# 13_USB3_0_power.net
KiCad netlist of a schematic drawn in Altium Designer
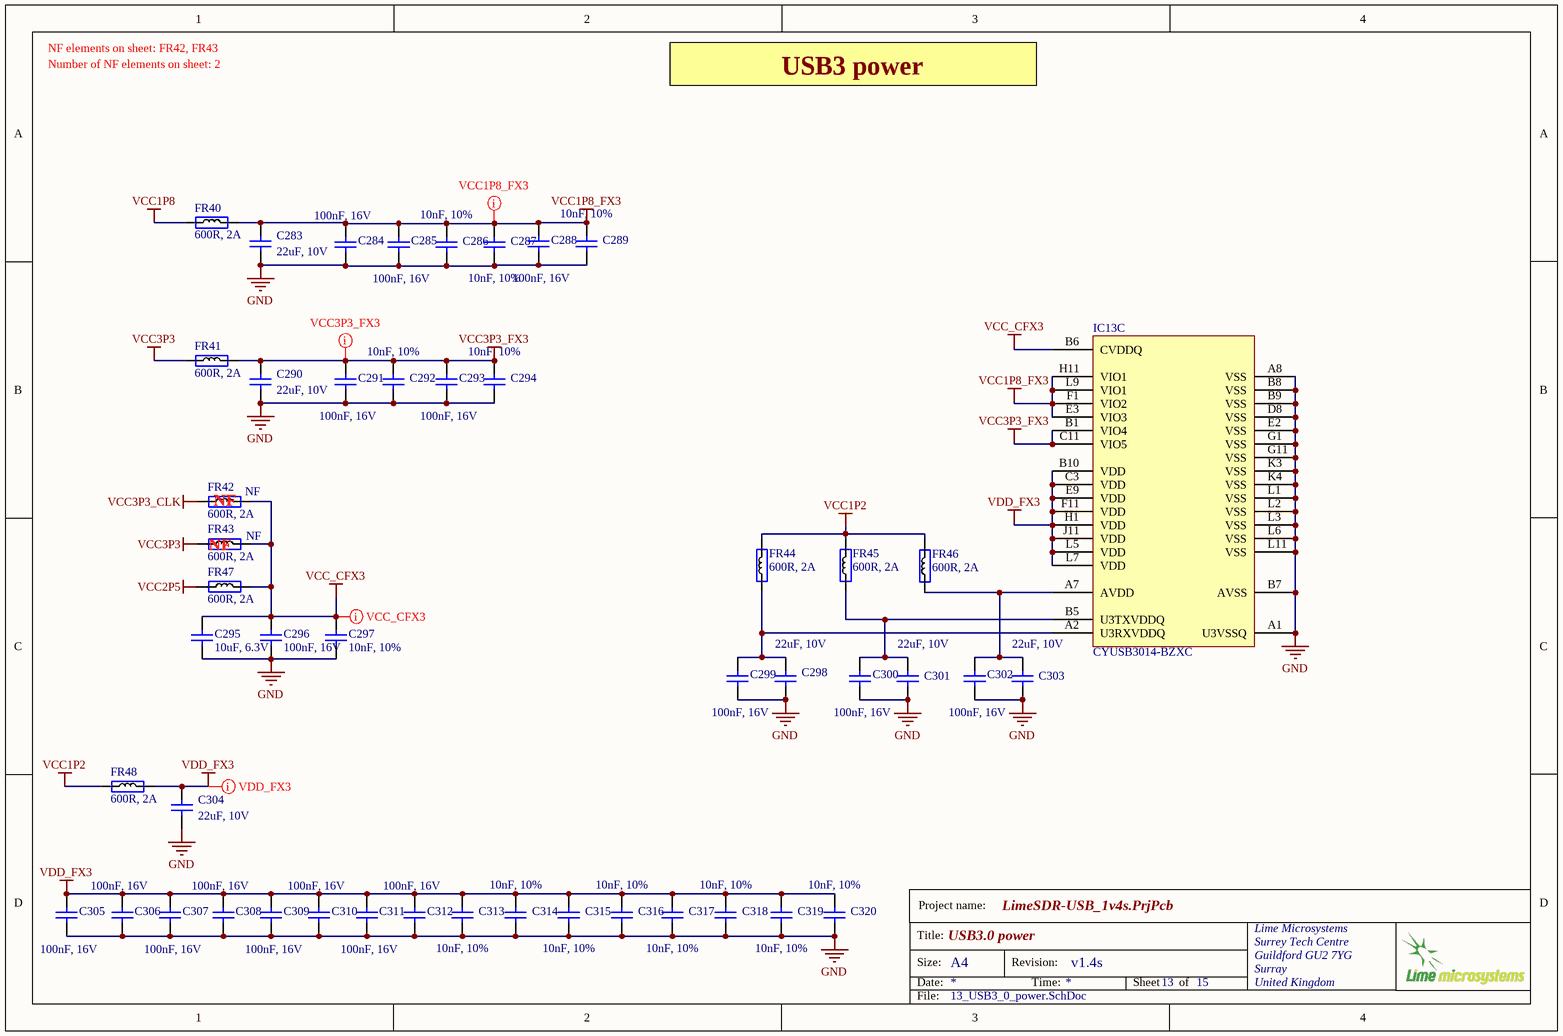
[diagram p0: 13_USB3_0_power.SchDoc]

(export (version "E")
  (design (tool "Eeschema 10.0.6"))
  (components
    (comp (ref "C283")
      (value "22uF, 10V")
      (footprint "CAP0603")
      (fields (field (name "TOLERANCE") "20 %") (field (name "MANUFACTURER") "TDK"))
      (libsource (lib "LimeFPGAboard_schLib") (part "Cap_0603"))
    )
    (comp (ref "C284")
      (value "100nF, 16V")
      (footprint "CAP0402")
      (fields
        (field (name "TOLERANCE") "10 %")
        (field (name "MANUFACTURER") "Murata Electronics")
        (field (name "MANUFACTURER PART NUMBER") "GRM155R71C104KA88D")
      )
      (libsource (lib "LimeFPGAboard_schLib") (part "Cap_0603"))
    )
    (comp (ref "C285")
      (value "100nF, 16V")
      (footprint "CAP0402")
      (fields
        (field (name "TOLERANCE") "10 %")
        (field (name "MANUFACTURER") "Murata Electronics")
        (field (name "MANUFACTURER PART NUMBER") "GRM155R71C104KA88D")
      )
      (libsource (lib "LimeFPGAboard_schLib") (part "Cap_0603"))
    )
    (comp (ref "C286")
      (value "10nF, 10%")
      (footprint "CAP0402")
      (fields (field (name "TOLERANCE") "±10%") (field (name "MANUFACTURER") "Yageo"))
      (libsource (lib "LimeFPGAboard_schLib") (part "Cap_0603"))
    )
    (comp (ref "C287")
      (value "10nF, 10%")
      (footprint "CAP0402")
      (fields (field (name "TOLERANCE") "±10%") (field (name "MANUFACTURER") "Yageo"))
      (libsource (lib "LimeFPGAboard_schLib") (part "Cap_0603"))
    )
    (comp (ref "C288")
      (value "100nF, 16V")
      (footprint "CAP0402")
      (fields
        (field (name "TOLERANCE") "10 %")
        (field (name "MANUFACTURER") "Murata Electronics")
        (field (name "MANUFACTURER PART NUMBER") "GRM155R71C104KA88D")
      )
      (libsource (lib "LimeFPGAboard_schLib") (part "Cap_0603"))
    )
    (comp (ref "C289")
      (value "10nF, 10%")
      (footprint "CAP0402")
      (fields (field (name "TOLERANCE") "±10%") (field (name "MANUFACTURER") "Yageo"))
      (libsource (lib "LimeFPGAboard_schLib") (part "Cap_0603"))
    )
    (comp (ref "C290")
      (value "22uF, 10V")
      (footprint "CAP0603")
      (fields (field (name "TOLERANCE") "20 %") (field (name "MANUFACTURER") "TDK"))
      (libsource (lib "LimeFPGAboard_schLib") (part "Cap_0603"))
    )
    (comp (ref "C291")
      (value "100nF, 16V")
      (footprint "CAP0402")
      (fields
        (field (name "TOLERANCE") "10 %")
        (field (name "MANUFACTURER") "Murata Electronics")
        (field (name "MANUFACTURER PART NUMBER") "GRM155R71C104KA88D")
      )
      (libsource (lib "LimeFPGAboard_schLib") (part "Cap_0603"))
    )
    (comp (ref "C292")
      (value "10nF, 10%")
      (footprint "CAP0402")
      (fields (field (name "TOLERANCE") "±10%") (field (name "MANUFACTURER") "Yageo"))
      (libsource (lib "LimeFPGAboard_schLib") (part "Cap_0603"))
    )
    (comp (ref "C293")
      (value "100nF, 16V")
      (footprint "CAP0402")
      (fields
        (field (name "TOLERANCE") "10 %")
        (field (name "MANUFACTURER") "Murata Electronics")
        (field (name "MANUFACTURER PART NUMBER") "GRM155R71C104KA88D")
      )
      (libsource (lib "LimeFPGAboard_schLib") (part "Cap_0603"))
    )
    (comp (ref "C294")
      (value "10nF, 10%")
      (footprint "CAP0402")
      (fields (field (name "TOLERANCE") "±10%") (field (name "MANUFACTURER") "Yageo"))
      (libsource (lib "LimeFPGAboard_schLib") (part "Cap_0603"))
    )
    (comp (ref "C295")
      (value "10uF, 6.3V")
      (footprint "CAP0603")
      (fields (field (name "TOLERANCE") "±20%") (field (name "MANUFACTURER") "Yageo"))
      (libsource (lib "LimeFPGAboard_schLib") (part "Cap_0603"))
    )
    (comp (ref "C296")
      (value "100nF, 16V")
      (footprint "CAP0402")
      (fields
        (field (name "TOLERANCE") "10 %")
        (field (name "MANUFACTURER") "Murata Electronics")
        (field (name "MANUFACTURER PART NUMBER") "GRM155R71C104KA88D")
      )
      (libsource (lib "LimeFPGAboard_schLib") (part "Cap_0603"))
    )
    (comp (ref "C297")
      (value "10nF, 10%")
      (footprint "CAP0402")
      (fields (field (name "TOLERANCE") "±10%") (field (name "MANUFACTURER") "Yageo"))
      (libsource (lib "LimeFPGAboard_schLib") (part "Cap_0603"))
    )
    (comp (ref "C298")
      (value "22uF, 10V")
      (footprint "CAP0603")
      (fields (field (name "TOLERANCE") "20 %") (field (name "MANUFACTURER") "TDK"))
      (libsource (lib "LimeFPGAboard_schLib") (part "Cap_0603"))
    )
    (comp (ref "C299")
      (value "100nF, 16V")
      (footprint "CAP0402")
      (fields
        (field (name "TOLERANCE") "10 %")
        (field (name "MANUFACTURER") "Murata Electronics")
        (field (name "MANUFACTURER PART NUMBER") "GRM155R71C104KA88D")
      )
      (libsource (lib "LimeFPGAboard_schLib") (part "Cap_0603"))
    )
    (comp (ref "C300")
      (value "100nF, 16V")
      (footprint "CAP0402")
      (fields
        (field (name "TOLERANCE") "10 %")
        (field (name "MANUFACTURER") "Murata Electronics")
        (field (name "MANUFACTURER PART NUMBER") "GRM155R71C104KA88D")
      )
      (libsource (lib "LimeFPGAboard_schLib") (part "Cap_0603"))
    )
    (comp (ref "C301")
      (value "22uF, 10V")
      (footprint "CAP0603")
      (fields (field (name "TOLERANCE") "20 %") (field (name "MANUFACTURER") "TDK"))
      (libsource (lib "LimeFPGAboard_schLib") (part "Cap_0603"))
    )
    (comp (ref "C302")
      (value "100nF, 16V")
      (footprint "CAP0402")
      (fields
        (field (name "TOLERANCE") "10 %")
        (field (name "MANUFACTURER") "Murata Electronics")
        (field (name "MANUFACTURER PART NUMBER") "GRM155R71C104KA88D")
      )
      (libsource (lib "LimeFPGAboard_schLib") (part "Cap_0603"))
    )
    (comp (ref "C303")
      (value "22uF, 10V")
      (footprint "CAP0603")
      (fields (field (name "TOLERANCE") "20 %") (field (name "MANUFACTURER") "TDK"))
      (libsource (lib "LimeFPGAboard_schLib") (part "Cap_0603"))
    )
    (comp (ref "C304")
      (value "22uF, 10V")
      (footprint "CAP0603")
      (fields (field (name "TOLERANCE") "20 %") (field (name "MANUFACTURER") "TDK"))
      (libsource (lib "LimeFPGAboard_schLib") (part "Cap_0603"))
    )
    (comp (ref "C305")
      (value "100nF, 16V")
      (footprint "CAP0402")
      (fields
        (field (name "TOLERANCE") "10 %")
        (field (name "MANUFACTURER") "Murata Electronics")
        (field (name "MANUFACTURER PART NUMBER") "GRM155R71C104KA88D")
      )
      (libsource (lib "LimeFPGAboard_schLib") (part "Cap_0603"))
    )
    (comp (ref "C306")
      (value "100nF, 16V")
      (footprint "CAP0402")
      (fields
        (field (name "TOLERANCE") "10 %")
        (field (name "MANUFACTURER") "Murata Electronics")
        (field (name "MANUFACTURER PART NUMBER") "GRM155R71C104KA88D")
      )
      (libsource (lib "LimeFPGAboard_schLib") (part "Cap_0603"))
    )
    (comp (ref "C307")
      (value "100nF, 16V")
      (footprint "CAP0402")
      (fields
        (field (name "TOLERANCE") "10 %")
        (field (name "MANUFACTURER") "Murata Electronics")
        (field (name "MANUFACTURER PART NUMBER") "GRM155R71C104KA88D")
      )
      (libsource (lib "LimeFPGAboard_schLib") (part "Cap_0603"))
    )
    (comp (ref "C308")
      (value "100nF, 16V")
      (footprint "CAP0402")
      (fields
        (field (name "TOLERANCE") "10 %")
        (field (name "MANUFACTURER") "Murata Electronics")
        (field (name "MANUFACTURER PART NUMBER") "GRM155R71C104KA88D")
      )
      (libsource (lib "LimeFPGAboard_schLib") (part "Cap_0603"))
    )
    (comp (ref "C309")
      (value "100nF, 16V")
      (footprint "CAP0402")
      (fields
        (field (name "TOLERANCE") "10 %")
        (field (name "MANUFACTURER") "Murata Electronics")
        (field (name "MANUFACTURER PART NUMBER") "GRM155R71C104KA88D")
      )
      (libsource (lib "LimeFPGAboard_schLib") (part "Cap_0603"))
    )
    (comp (ref "C310")
      (value "100nF, 16V")
      (footprint "CAP0402")
      (fields
        (field (name "TOLERANCE") "10 %")
        (field (name "MANUFACTURER") "Murata Electronics")
        (field (name "MANUFACTURER PART NUMBER") "GRM155R71C104KA88D")
      )
      (libsource (lib "LimeFPGAboard_schLib") (part "Cap_0603"))
    )
    (comp (ref "C311")
      (value "100nF, 16V")
      (footprint "CAP0402")
      (fields
        (field (name "TOLERANCE") "10 %")
        (field (name "MANUFACTURER") "Murata Electronics")
        (field (name "MANUFACTURER PART NUMBER") "GRM155R71C104KA88D")
      )
      (libsource (lib "LimeFPGAboard_schLib") (part "Cap_0603"))
    )
    (comp (ref "C312")
      (value "100nF, 16V")
      (footprint "CAP0402")
      (fields
        (field (name "TOLERANCE") "10 %")
        (field (name "MANUFACTURER") "Murata Electronics")
        (field (name "MANUFACTURER PART NUMBER") "GRM155R71C104KA88D")
      )
      (libsource (lib "LimeFPGAboard_schLib") (part "Cap_0603"))
    )
    (comp (ref "C313")
      (value "10nF, 10%")
      (footprint "CAP0402")
      (fields (field (name "TOLERANCE") "±10%") (field (name "MANUFACTURER") "Yageo"))
      (libsource (lib "LimeFPGAboard_schLib") (part "Cap_0603"))
    )
    (comp (ref "C314")
      (value "10nF, 10%")
      (footprint "CAP0402")
      (fields (field (name "TOLERANCE") "±10%") (field (name "MANUFACTURER") "Yageo"))
      (libsource (lib "LimeFPGAboard_schLib") (part "Cap_0603"))
    )
    (comp (ref "C315")
      (value "10nF, 10%")
      (footprint "CAP0402")
      (fields (field (name "TOLERANCE") "±10%") (field (name "MANUFACTURER") "Yageo"))
      (libsource (lib "LimeFPGAboard_schLib") (part "Cap_0603"))
    )
    (comp (ref "C316")
      (value "10nF, 10%")
      (footprint "CAP0402")
      (fields (field (name "TOLERANCE") "±10%") (field (name "MANUFACTURER") "Yageo"))
      (libsource (lib "LimeFPGAboard_schLib") (part "Cap_0603"))
    )
    (comp (ref "C317")
      (value "10nF, 10%")
      (footprint "CAP0402")
      (fields (field (name "TOLERANCE") "±10%") (field (name "MANUFACTURER") "Yageo"))
      (libsource (lib "LimeFPGAboard_schLib") (part "Cap_0603"))
    )
    (comp (ref "C318")
      (value "10nF, 10%")
      (footprint "CAP0402")
      (fields (field (name "TOLERANCE") "±10%") (field (name "MANUFACTURER") "Yageo"))
      (libsource (lib "LimeFPGAboard_schLib") (part "Cap_0603"))
    )
    (comp (ref "C319")
      (value "10nF, 10%")
      (footprint "CAP0402")
      (fields (field (name "TOLERANCE") "±10%") (field (name "MANUFACTURER") "Yageo"))
      (libsource (lib "LimeFPGAboard_schLib") (part "Cap_0603"))
    )
    (comp (ref "C320")
      (value "10nF, 10%")
      (footprint "CAP0402")
      (fields (field (name "TOLERANCE") "±10%") (field (name "MANUFACTURER") "Yageo"))
      (libsource (lib "LimeFPGAboard_schLib") (part "Cap_0603"))
    )
    (comp (ref "FR40")
      (value "600R, 2A")
      (footprint "RES0805")
      (fields (field (name "MANUFACTURER") "TDK Corporation"))
      (libsource (lib "LimeFPGAboard_schLib") (part "Ferrite"))
    )
    (comp (ref "FR41")
      (value "600R, 2A")
      (footprint "RES0805")
      (fields (field (name "MANUFACTURER") "TDK Corporation"))
      (libsource (lib "LimeFPGAboard_schLib") (part "Ferrite"))
    )
    (comp (ref "FR42")
      (value "600R, 2A")
      (footprint "RES0805")
      (fields (field (name "MANUFACTURER") "TDK Corporation") (field (name "ASSEMBLY INFO") "NF"))
      (libsource (lib "") (part "Ferrite_1"))
    )
    (comp (ref "FR43")
      (value "600R, 2A")
      (footprint "RES0805")
      (fields (field (name "MANUFACTURER") "TDK Corporation") (field (name "ASSEMBLY INFO") "NF"))
      (libsource (lib "") (part "Ferrite_1"))
    )
    (comp (ref "FR44")
      (value "600R, 2A")
      (footprint "RES0805")
      (fields (field (name "MANUFACTURER") "TDK Corporation"))
      (libsource (lib "LimeFPGAboard_schLib") (part "Ferrite"))
    )
    (comp (ref "FR45")
      (value "600R, 2A")
      (footprint "RES0805")
      (fields (field (name "MANUFACTURER") "TDK Corporation"))
      (libsource (lib "LimeFPGAboard_schLib") (part "Ferrite"))
    )
    (comp (ref "FR46")
      (value "600R, 2A")
      (footprint "RES0805")
      (fields (field (name "MANUFACTURER") "TDK Corporation"))
      (libsource (lib "LimeFPGAboard_schLib") (part "Ferrite"))
    )
    (comp (ref "FR47")
      (value "600R, 2A")
      (footprint "RES0805")
      (fields (field (name "MANUFACTURER") "TDK Corporation"))
      (libsource (lib "") (part "Ferrite_1"))
    )
    (comp (ref "FR48")
      (value "600R, 2A")
      (footprint "RES0805")
      (fields (field (name "MANUFACTURER") "TDK Corporation"))
      (libsource (lib "LimeFPGAboard_schLib") (part "Ferrite"))
    )
    (comp (ref "IC13")
      (value "CYUSB3014-BZXC")
      (footprint "CYP-BZX121")
      (description "EZ-USB(R) FX3: SuperSpeed USB Controller, 512 KB, 60 I/Os, 0 to 70 degC, 121-Pin FBGA (BZX121)")
      (fields (field (name "MANUFACTURER") "Cypress Semiconductor Corp"))
      (libsource (lib "LimeMicroAltiumLib_schLib") (part "CYUSB3014-BZXC"))
    )
  )
  (nets
    (net (code "1") (name "GND") (class "Default")
      (node (ref "C283") (pin "1") (pinfunction "1_1") (pintype "passive"))
      (node (ref "C284") (pin "2") (pinfunction "2_2") (pintype "passive"))
      (node (ref "C285") (pin "2") (pinfunction "2_2") (pintype "passive"))
      (node (ref "C286") (pin "1") (pinfunction "1_1") (pintype "passive"))
      (node (ref "C287") (pin "1") (pinfunction "1_1") (pintype "passive"))
      (node (ref "C288") (pin "2") (pinfunction "2_2") (pintype "passive"))
      (node (ref "C289") (pin "1") (pinfunction "1_1") (pintype "passive"))
      (node (ref "C290") (pin "1") (pinfunction "1_1") (pintype "passive"))
      (node (ref "C291") (pin "2") (pinfunction "2_2") (pintype "passive"))
      (node (ref "C292") (pin "1") (pinfunction "1_1") (pintype "passive"))
      (node (ref "C293") (pin "2") (pinfunction "2_2") (pintype "passive"))
      (node (ref "C294") (pin "1") (pinfunction "1_1") (pintype "passive"))
      (node (ref "C295") (pin "1") (pinfunction "1_1") (pintype "passive"))
      (node (ref "C296") (pin "2") (pinfunction "2_2") (pintype "passive"))
      (node (ref "C297") (pin "1") (pinfunction "1_1") (pintype "passive"))
      (node (ref "C298") (pin "1") (pinfunction "1_1") (pintype "passive"))
      (node (ref "C299") (pin "2") (pinfunction "2_2") (pintype "passive"))
      (node (ref "C300") (pin "2") (pinfunction "2_2") (pintype "passive"))
      (node (ref "C301") (pin "1") (pinfunction "1_1") (pintype "passive"))
      (node (ref "C302") (pin "2") (pinfunction "2_2") (pintype "passive"))
      (node (ref "C303") (pin "1") (pinfunction "1_1") (pintype "passive"))
      (node (ref "C304") (pin "1") (pinfunction "1_1") (pintype "passive"))
      (node (ref "C305") (pin "2") (pinfunction "2_2") (pintype "passive"))
      (node (ref "C306") (pin "2") (pinfunction "2_2") (pintype "passive"))
      (node (ref "C307") (pin "2") (pinfunction "2_2") (pintype "passive"))
      (node (ref "C308") (pin "2") (pinfunction "2_2") (pintype "passive"))
      (node (ref "C309") (pin "2") (pinfunction "2_2") (pintype "passive"))
      (node (ref "C310") (pin "2") (pinfunction "2_2") (pintype "passive"))
      (node (ref "C311") (pin "2") (pinfunction "2_2") (pintype "passive"))
      (node (ref "C312") (pin "2") (pinfunction "2_2") (pintype "passive"))
      (node (ref "C313") (pin "1") (pinfunction "1_1") (pintype "passive"))
      (node (ref "C314") (pin "1") (pinfunction "1_1") (pintype "passive"))
      (node (ref "C315") (pin "1") (pinfunction "1_1") (pintype "passive"))
      (node (ref "C316") (pin "1") (pinfunction "1_1") (pintype "passive"))
      (node (ref "C317") (pin "1") (pinfunction "1_1") (pintype "passive"))
      (node (ref "C318") (pin "1") (pinfunction "1_1") (pintype "passive"))
      (node (ref "C319") (pin "1") (pinfunction "1_1") (pintype "passive"))
      (node (ref "C320") (pin "1") (pinfunction "1_1") (pintype "passive"))
      (node (ref "IC13") (pin "A1") (pinfunction "U3VSSQ_A1") (pintype "power_in"))
      (node (ref "IC13") (pin "A8") (pinfunction "VSS_A8") (pintype "power_in"))
      (node (ref "IC13") (pin "B7") (pinfunction "AVSS_B7") (pintype "power_in"))
      (node (ref "IC13") (pin "B8") (pinfunction "VSS_B8") (pintype "power_in"))
      (node (ref "IC13") (pin "B9") (pinfunction "VSS_B9") (pintype "power_in"))
      (node (ref "IC13") (pin "D8") (pinfunction "VSS_D8") (pintype "power_in"))
      (node (ref "IC13") (pin "E2") (pinfunction "VSS_E2") (pintype "power_in"))
      (node (ref "IC13") (pin "G1") (pinfunction "VSS_G1") (pintype "power_in"))
      (node (ref "IC13") (pin "G11") (pinfunction "VSS_G11") (pintype "power_in"))
      (node (ref "IC13") (pin "K3") (pinfunction "VSS_K3") (pintype "power_in"))
      (node (ref "IC13") (pin "K4") (pinfunction "VSS_K4") (pintype "power_in"))
      (node (ref "IC13") (pin "L1") (pinfunction "VSS_L1") (pintype "power_in"))
      (node (ref "IC13") (pin "L11") (pinfunction "VSS_L11") (pintype "power_in"))
      (node (ref "IC13") (pin "L2") (pinfunction "VSS_L2") (pintype "power_in"))
      (node (ref "IC13") (pin "L3") (pinfunction "VSS_L3") (pintype "power_in"))
      (node (ref "IC13") (pin "L6") (pinfunction "VSS_L6") (pintype "power_in"))
    )
    (net (code "2") (name "Net-(IC13C-AVDD)") (class "Default")
      (node (ref "C302") (pin "1") (pinfunction "1_1") (pintype "passive"))
      (node (ref "C303") (pin "2") (pinfunction "2_2") (pintype "passive"))
      (node (ref "FR46") (pin "1") (pinfunction "1_1") (pintype "passive"))
      (node (ref "IC13") (pin "A7") (pinfunction "AVDD_A7") (pintype "power_in"))
    )
    (net (code "3") (name "Net-(IC13C-U3RXVDDQ)") (class "Default")
      (node (ref "C298") (pin "2") (pinfunction "2_2") (pintype "passive"))
      (node (ref "C299") (pin "1") (pinfunction "1_1") (pintype "passive"))
      (node (ref "FR44") (pin "1") (pinfunction "1_1") (pintype "passive"))
      (node (ref "IC13") (pin "A2") (pinfunction "U3RXVDDQ_A2") (pintype "power_in"))
    )
    (net (code "4") (name "Net-(IC13C-U3TXVDDQ)") (class "Default")
      (node (ref "C300") (pin "1") (pinfunction "1_1") (pintype "passive"))
      (node (ref "C301") (pin "2") (pinfunction "2_2") (pintype "passive"))
      (node (ref "FR45") (pin "1") (pinfunction "1_1") (pintype "passive"))
      (node (ref "IC13") (pin "B5") (pinfunction "U3TXVDDQ_B5") (pintype "power_in"))
    )
    (net (code "5") (name "VCC1P2") (class "Default")
      (node (ref "FR44") (pin "2") (pinfunction "2_2") (pintype "passive"))
      (node (ref "FR45") (pin "2") (pinfunction "2_2") (pintype "passive"))
      (node (ref "FR46") (pin "2") (pinfunction "2_2") (pintype "passive"))
      (node (ref "FR48") (pin "1") (pinfunction "1_1") (pintype "passive"))
    )
    (net (code "6") (name "VCC1P8") (class "Default")
      (node (ref "FR40") (pin "1") (pinfunction "1_1") (pintype "passive"))
    )
    (net (code "7") (name "VCC1P8_FX3") (class "Default")
      (node (ref "C283") (pin "2") (pinfunction "2_2") (pintype "passive"))
      (node (ref "C284") (pin "1") (pinfunction "1_1") (pintype "passive"))
      (node (ref "C285") (pin "1") (pinfunction "1_1") (pintype "passive"))
      (node (ref "C286") (pin "2") (pinfunction "2_2") (pintype "passive"))
      (node (ref "C287") (pin "2") (pinfunction "2_2") (pintype "passive"))
      (node (ref "C288") (pin "1") (pinfunction "1_1") (pintype "passive"))
      (node (ref "C289") (pin "2") (pinfunction "2_2") (pintype "passive"))
      (node (ref "FR40") (pin "2") (pinfunction "2_2") (pintype "passive"))
      (node (ref "IC13") (pin "E3") (pinfunction "VIO3_E3") (pintype "power_in"))
      (node (ref "IC13") (pin "F1") (pinfunction "VIO2_F1") (pintype "power_in"))
      (node (ref "IC13") (pin "H11") (pinfunction "VIO1_H11") (pintype "power_in"))
      (node (ref "IC13") (pin "L9") (pinfunction "VIO1_L9") (pintype "power_in"))
    )
    (net (code "8") (name "VCC2P5") (class "Default")
      (node (ref "FR47") (pin "2") (pinfunction "2_2") (pintype "passive"))
    )
    (net (code "9") (name "VCC3P3") (class "Default")
      (node (ref "FR41") (pin "1") (pinfunction "1_1") (pintype "passive"))
      (node (ref "FR43") (pin "2") (pinfunction "2_2") (pintype "passive"))
    )
    (net (code "10") (name "VCC3P3_CLK") (class "Default")
      (node (ref "FR42") (pin "2") (pinfunction "2_2") (pintype "passive"))
    )
    (net (code "11") (name "VCC3P3_FX3") (class "Default")
      (node (ref "C290") (pin "2") (pinfunction "2_2") (pintype "passive"))
      (node (ref "C291") (pin "1") (pinfunction "1_1") (pintype "passive"))
      (node (ref "C292") (pin "2") (pinfunction "2_2") (pintype "passive"))
      (node (ref "C293") (pin "1") (pinfunction "1_1") (pintype "passive"))
      (node (ref "C294") (pin "2") (pinfunction "2_2") (pintype "passive"))
      (node (ref "FR41") (pin "2") (pinfunction "2_2") (pintype "passive"))
      (node (ref "IC13") (pin "B1") (pinfunction "VIO4_B1") (pintype "power_in"))
      (node (ref "IC13") (pin "C11") (pinfunction "VIO5_C11") (pintype "power_in"))
    )
    (net (code "12") (name "VCC_CFX3") (class "Default")
      (node (ref "C295") (pin "2") (pinfunction "2_2") (pintype "passive"))
      (node (ref "C296") (pin "1") (pinfunction "1_1") (pintype "passive"))
      (node (ref "C297") (pin "2") (pinfunction "2_2") (pintype "passive"))
      (node (ref "FR42") (pin "1") (pinfunction "1_1") (pintype "passive"))
      (node (ref "FR43") (pin "1") (pinfunction "1_1") (pintype "passive"))
      (node (ref "FR47") (pin "1") (pinfunction "1_1") (pintype "passive"))
      (node (ref "IC13") (pin "B6") (pinfunction "CVDDQ_B6") (pintype "power_in"))
    )
    (net (code "13") (name "VDD_FX3") (class "Default")
      (node (ref "C304") (pin "2") (pinfunction "2_2") (pintype "passive"))
      (node (ref "C305") (pin "1") (pinfunction "1_1") (pintype "passive"))
      (node (ref "C306") (pin "1") (pinfunction "1_1") (pintype "passive"))
      (node (ref "C307") (pin "1") (pinfunction "1_1") (pintype "passive"))
      (node (ref "C308") (pin "1") (pinfunction "1_1") (pintype "passive"))
      (node (ref "C309") (pin "1") (pinfunction "1_1") (pintype "passive"))
      (node (ref "C310") (pin "1") (pinfunction "1_1") (pintype "passive"))
      (node (ref "C311") (pin "1") (pinfunction "1_1") (pintype "passive"))
      (node (ref "C312") (pin "1") (pinfunction "1_1") (pintype "passive"))
      (node (ref "C313") (pin "2") (pinfunction "2_2") (pintype "passive"))
      (node (ref "C314") (pin "2") (pinfunction "2_2") (pintype "passive"))
      (node (ref "C315") (pin "2") (pinfunction "2_2") (pintype "passive"))
      (node (ref "C316") (pin "2") (pinfunction "2_2") (pintype "passive"))
      (node (ref "C317") (pin "2") (pinfunction "2_2") (pintype "passive"))
      (node (ref "C318") (pin "2") (pinfunction "2_2") (pintype "passive"))
      (node (ref "C319") (pin "2") (pinfunction "2_2") (pintype "passive"))
      (node (ref "C320") (pin "2") (pinfunction "2_2") (pintype "passive"))
      (node (ref "FR48") (pin "2") (pinfunction "2_2") (pintype "passive"))
      (node (ref "IC13") (pin "B10") (pinfunction "VDD_B10") (pintype "power_in"))
      (node (ref "IC13") (pin "C3") (pinfunction "VDD_C3") (pintype "power_in"))
      (node (ref "IC13") (pin "E9") (pinfunction "VDD_E9") (pintype "power_in"))
      (node (ref "IC13") (pin "F11") (pinfunction "VDD_F11") (pintype "power_in"))
      (node (ref "IC13") (pin "H1") (pinfunction "VDD_H1") (pintype "power_in"))
      (node (ref "IC13") (pin "J11") (pinfunction "VDD_J11") (pintype "power_in"))
      (node (ref "IC13") (pin "L5") (pinfunction "VDD_L5") (pintype "power_in"))
      (node (ref "IC13") (pin "L7") (pinfunction "VDD_L7") (pintype "power_in"))
    )
  )
)
